# freq_meter_low.net
KiCad netlist of a schematic drawn in EAGLE
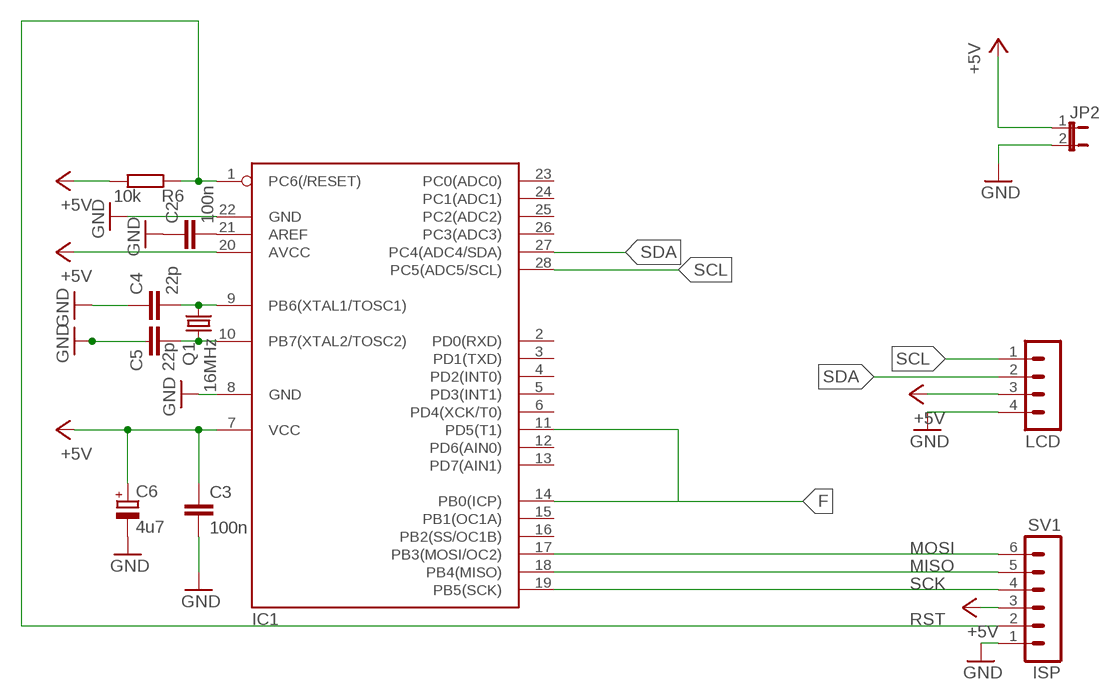
[diagram p0: schematic, sheet 1]

(export (version "E")
  (design (tool "Eeschema 10.0.6"))
  (components
    (comp (ref "C2")
      (value "100n")
      (footprint "eagle-import:C025-024X044")
      (libsource (lib "eagle-import") (part "C-EU025-024X044"))
    )
    (comp (ref "C3")
      (value "100n")
      (footprint "eagle-import:C025-024X044")
      (libsource (lib "eagle-import") (part "C-EU025-024X044"))
    )
    (comp (ref "C4")
      (value "22p")
      (footprint "eagle-import:C025-024X044")
      (libsource (lib "eagle-import") (part "C-EU025-024X044"))
    )
    (comp (ref "C5")
      (value "22p")
      (footprint "eagle-import:C050-025X075")
      (libsource (lib "eagle-import") (part "C-EU050-025X075"))
    )
    (comp (ref "C6")
      (value "4u7")
      (footprint "eagle-import:TT2D5")
      (libsource (lib "eagle-import") (part "CPOL-EUTT2D5"))
    )
    (comp (ref "IC1")
      (value "MEGA8-P")
      (footprint "eagle-import:DIL28-3")
      (libsource (lib "eagle-import") (part "MEGA8-P"))
    )
    (comp (ref "JP2")
      (value "JP1E")
      (footprint "eagle-import:JP1")
      (libsource (lib "eagle-import") (part "JP1E"))
    )
    (comp (ref "LCD")
      (value "MA04-1")
      (footprint "eagle-import:MA04-1")
      (libsource (lib "eagle-import") (part "MA04-1"))
    )
    (comp (ref "Q1")
      (value "16MHz")
      (footprint "eagle-import:TC26V")
      (libsource (lib "eagle-import") (part "CRYSTALTC26V"))
    )
    (comp (ref "R6")
      (value "10k")
      (footprint "eagle-import:0204_5")
      (libsource (lib "eagle-import") (part "R-EU_0204/5"))
    )
    (comp (ref "SV1")
      (value "ISP")
      (footprint "eagle-import:MA06-1")
      (libsource (lib "eagle-import") (part "MA06-1"))
    )
  )
  (nets
    (net (code "1") (name "+5V") (class "Default")
      (node (ref "C3") (pin "1") (pinfunction "1_1") (pintype "passive"))
      (node (ref "C6") (pin "+") (pinfunction "+_+") (pintype "passive"))
      (node (ref "IC1") (pin "20") (pinfunction "AVCC_20") (pintype "power_in"))
      (node (ref "IC1") (pin "7") (pinfunction "VCC_7") (pintype "power_in"))
      (node (ref "JP2") (pin "1") (pinfunction "1_1") (pintype "passive"))
      (node (ref "LCD") (pin "3") (pinfunction "3_3") (pintype "passive"))
      (node (ref "R6") (pin "1") (pinfunction "1_1") (pintype "passive"))
      (node (ref "SV1") (pin "3") (pinfunction "3_3") (pintype "passive"))
    )
    (net (code "2") (name "/MISO") (class "Default")
      (node (ref "IC1") (pin "18") (pinfunction "PB4(MISO)_18") (pintype "bidirectional"))
      (node (ref "SV1") (pin "5") (pinfunction "5_5") (pintype "passive"))
    )
    (net (code "3") (name "/MOSI") (class "Default")
      (node (ref "IC1") (pin "17") (pinfunction "PB3(MOSI/OC2)_17") (pintype "bidirectional"))
      (node (ref "SV1") (pin "6") (pinfunction "6_6") (pintype "passive"))
    )
    (net (code "4") (name "/RST") (class "Default")
      (node (ref "IC1") (pin "1") (pinfunction "PC6(/RESET)_1") (pintype "bidirectional"))
      (node (ref "R6") (pin "2") (pinfunction "2_2") (pintype "passive"))
      (node (ref "SV1") (pin "2") (pinfunction "2_2") (pintype "passive"))
    )
    (net (code "5") (name "/SCK") (class "Default")
      (node (ref "IC1") (pin "19") (pinfunction "PB5(SCK)_19") (pintype "bidirectional"))
      (node (ref "SV1") (pin "4") (pinfunction "4_4") (pintype "passive"))
    )
    (net (code "6") (name "F") (class "Default")
      (node (ref "IC1") (pin "11") (pinfunction "PD5(T1)_11") (pintype "bidirectional"))
      (node (ref "IC1") (pin "14") (pinfunction "PB0(ICP)_14") (pintype "bidirectional"))
    )
    (net (code "7") (name "GND") (class "Default")
      (node (ref "C2") (pin "1") (pinfunction "1_1") (pintype "passive"))
      (node (ref "C3") (pin "2") (pinfunction "2_2") (pintype "passive"))
      (node (ref "C4") (pin "1") (pinfunction "1_1") (pintype "passive"))
      (node (ref "C5") (pin "1") (pinfunction "1_1") (pintype "passive"))
      (node (ref "C6") (pin "-") (pinfunction "-_-") (pintype "passive"))
      (node (ref "IC1") (pin "22") (pinfunction "GND_22") (pintype "power_in"))
      (node (ref "IC1") (pin "8") (pinfunction "GND_8") (pintype "power_in"))
      (node (ref "JP2") (pin "2") (pinfunction "2_2") (pintype "passive"))
      (node (ref "LCD") (pin "4") (pinfunction "4_4") (pintype "passive"))
      (node (ref "SV1") (pin "1") (pinfunction "1_1") (pintype "passive"))
    )
    (net (code "8") (name "Net-(IC1-AREF)") (class "Default")
      (node (ref "C2") (pin "2") (pinfunction "2_2") (pintype "passive"))
      (node (ref "IC1") (pin "21") (pinfunction "AREF_21") (pintype "passive"))
    )
    (net (code "9") (name "Net-(IC1-PB6(XTAL1{slash}TOSC1))") (class "Default")
      (node (ref "C4") (pin "2") (pinfunction "2_2") (pintype "passive"))
      (node (ref "IC1") (pin "9") (pinfunction "PB6(XTAL1/TOSC1)_9") (pintype "bidirectional"))
      (node (ref "Q1") (pin "2") (pinfunction "2_2") (pintype "passive"))
    )
    (net (code "10") (name "Net-(IC1-PB7(XTAL2{slash}TOSC2))") (class "Default")
      (node (ref "C5") (pin "2") (pinfunction "2_2") (pintype "passive"))
      (node (ref "IC1") (pin "10") (pinfunction "PB7(XTAL2/TOSC2)_10") (pintype "bidirectional"))
      (node (ref "Q1") (pin "1") (pinfunction "1_1") (pintype "passive"))
    )
    (net (code "11") (name "SCL") (class "Default")
      (node (ref "IC1") (pin "28") (pinfunction "PC5(ADC5/SCL)_28") (pintype "bidirectional"))
      (node (ref "LCD") (pin "1") (pinfunction "1_1") (pintype "passive"))
    )
    (net (code "12") (name "SDA") (class "Default")
      (node (ref "IC1") (pin "27") (pinfunction "PC4(ADC4/SDA)_27") (pintype "bidirectional"))
      (node (ref "LCD") (pin "2") (pinfunction "2_2") (pintype "passive"))
    )
    (net (code "13") (name "unconnected-(IC1-PB1(OC1A)-Pad15)") (class "Default")
      (node (ref "IC1") (pin "15") (pinfunction "PB1(OC1A)_15") (pintype "bidirectional"))
    )
    (net (code "14") (name "unconnected-(IC1-PB2(SS{slash}OC1B)-Pad16)") (class "Default")
      (node (ref "IC1") (pin "16") (pinfunction "PB2(SS/OC1B)_16") (pintype "bidirectional"))
    )
    (net (code "15") (name "unconnected-(IC1-PC0(ADC0)-Pad23)") (class "Default")
      (node (ref "IC1") (pin "23") (pinfunction "PC0(ADC0)_23") (pintype "bidirectional"))
    )
    (net (code "16") (name "unconnected-(IC1-PC1(ADC1)-Pad24)") (class "Default")
      (node (ref "IC1") (pin "24") (pinfunction "PC1(ADC1)_24") (pintype "bidirectional"))
    )
    (net (code "17") (name "unconnected-(IC1-PC2(ADC2)-Pad25)") (class "Default")
      (node (ref "IC1") (pin "25") (pinfunction "PC2(ADC2)_25") (pintype "bidirectional"))
    )
    (net (code "18") (name "unconnected-(IC1-PC3(ADC3)-Pad26)") (class "Default")
      (node (ref "IC1") (pin "26") (pinfunction "PC3(ADC3)_26") (pintype "bidirectional"))
    )
    (net (code "19") (name "unconnected-(IC1-PD0(RXD)-Pad2)") (class "Default")
      (node (ref "IC1") (pin "2") (pinfunction "PD0(RXD)_2") (pintype "bidirectional"))
    )
    (net (code "20") (name "unconnected-(IC1-PD1(TXD)-Pad3)") (class "Default")
      (node (ref "IC1") (pin "3") (pinfunction "PD1(TXD)_3") (pintype "bidirectional"))
    )
    (net (code "21") (name "unconnected-(IC1-PD2(INT0)-Pad4)") (class "Default")
      (node (ref "IC1") (pin "4") (pinfunction "PD2(INT0)_4") (pintype "bidirectional"))
    )
    (net (code "22") (name "unconnected-(IC1-PD3(INT1)-Pad5)") (class "Default")
      (node (ref "IC1") (pin "5") (pinfunction "PD3(INT1)_5") (pintype "bidirectional"))
    )
    (net (code "23") (name "unconnected-(IC1-PD4(XCK{slash}T0)-Pad6)") (class "Default")
      (node (ref "IC1") (pin "6") (pinfunction "PD4(XCK/T0)_6") (pintype "bidirectional"))
    )
    (net (code "24") (name "unconnected-(IC1-PD6(AIN0)-Pad12)") (class "Default")
      (node (ref "IC1") (pin "12") (pinfunction "PD6(AIN0)_12") (pintype "bidirectional"))
    )
    (net (code "25") (name "unconnected-(IC1-PD7(AIN1)-Pad13)") (class "Default")
      (node (ref "IC1") (pin "13") (pinfunction "PD7(AIN1)_13") (pintype "bidirectional"))
    )
  )
)
